# B301D.net
KiCad netlist of a schematic drawn in EAGLE
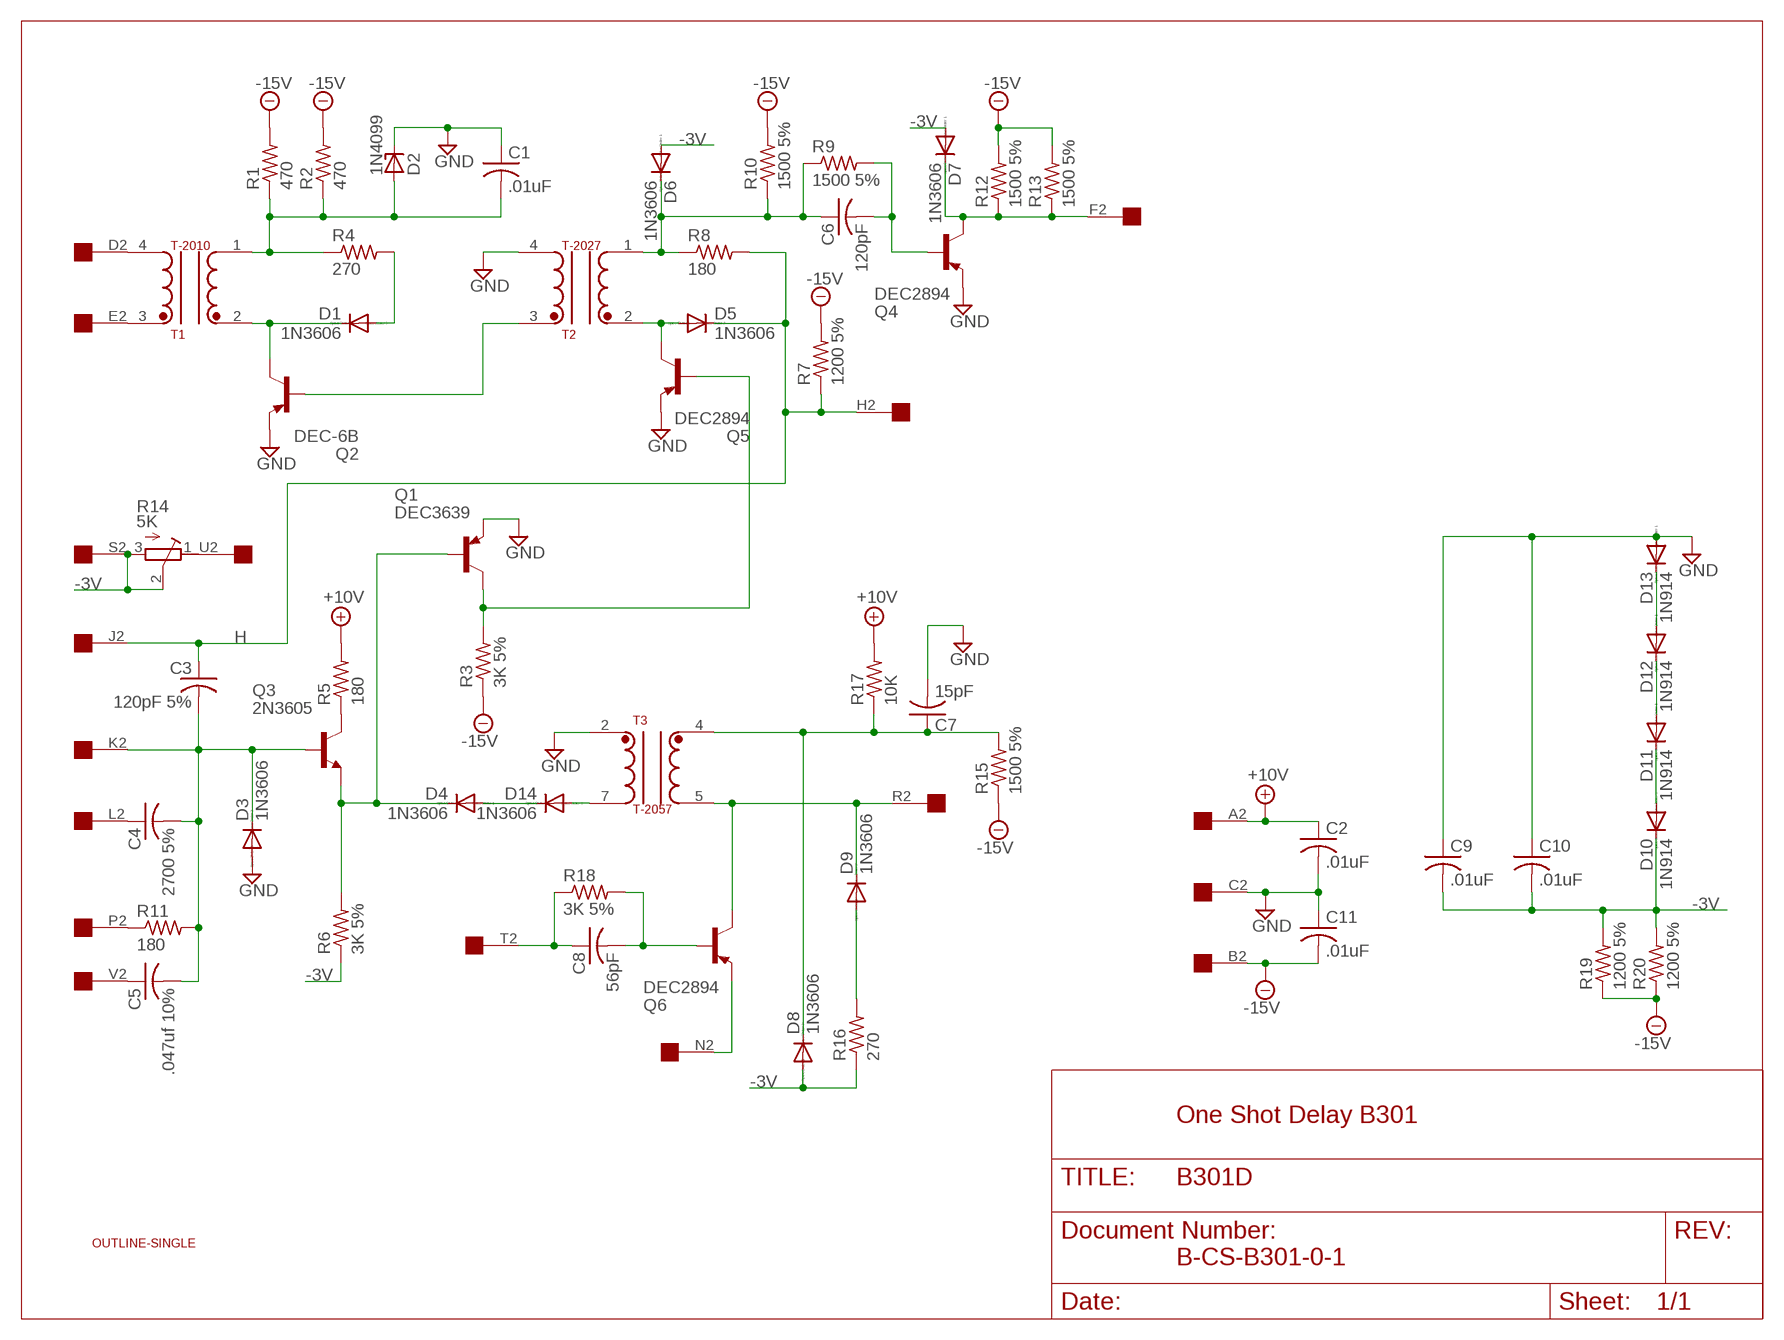
[diagram p0: schematic, sheet 1]

(export (version "E")
  (design (tool "Eeschema 10.0.6"))
  (components
    (comp (ref "C1")
      (value ".01uF")
      (footprint "eagle-import:C063-025X075")
      (libsource (lib "eagle-import") (part "C-US"))
    )
    (comp (ref "C2")
      (value ".01uF")
      (footprint "eagle-import:C063-025X075")
      (libsource (lib "eagle-import") (part "C-US"))
    )
    (comp (ref "C3")
      (value "120pF 5%")
      (footprint "eagle-import:C150-054X183")
      (libsource (lib "eagle-import") (part "C-US150-054X183"))
    )
    (comp (ref "C4")
      (value "2700 5%")
      (footprint "eagle-import:C102-043X133")
      (libsource (lib "eagle-import") (part "C-US102-043X133"))
    )
    (comp (ref "C5")
      (value ".047uf 10%")
      (footprint "eagle-import:C225-062X268")
      (libsource (lib "eagle-import") (part "C-US225-062X268"))
    )
    (comp (ref "C6")
      (value "120pF")
      (footprint "eagle-import:C150-054X183")
      (libsource (lib "eagle-import") (part "C-US150-054X183"))
    )
    (comp (ref "C7")
      (value "15pF")
      (footprint "eagle-import:C150-054X183")
      (libsource (lib "eagle-import") (part "C-US150-054X183"))
    )
    (comp (ref "C8")
      (value "56pF")
      (footprint "eagle-import:C150-054X183")
      (libsource (lib "eagle-import") (part "C-US150-054X183"))
    )
    (comp (ref "C9")
      (value ".01uF")
      (footprint "eagle-import:C063-025X075")
      (libsource (lib "eagle-import") (part "C-US"))
    )
    (comp (ref "C10")
      (value ".01uF")
      (footprint "eagle-import:C063-025X075")
      (libsource (lib "eagle-import") (part "C-US"))
    )
    (comp (ref "C11")
      (value ".01uF")
      (footprint "eagle-import:C063-025X075")
      (libsource (lib "eagle-import") (part "C-US"))
    )
    (comp (ref "D1")
      (value "1N3606")
      (footprint "eagle-import:DO35-10")
      (libsource (lib "eagle-import") (part "1N4148DO35-10"))
    )
    (comp (ref "D2")
      (value "1N4099")
      (footprint "eagle-import:DO35Z10")
      (libsource (lib "eagle-import") (part "ZENER-DIODEDO35Z10"))
    )
    (comp (ref "D3")
      (value "1N3606")
      (footprint "eagle-import:DO35-10")
      (libsource (lib "eagle-import") (part "1N4148DO35-10"))
    )
    (comp (ref "D4")
      (value "1N3606")
      (footprint "eagle-import:DO35-10")
      (libsource (lib "eagle-import") (part "1N4148DO35-10"))
    )
    (comp (ref "D5")
      (value "1N3606")
      (footprint "eagle-import:DO35-10")
      (libsource (lib "eagle-import") (part "1N4148DO35-10"))
    )
    (comp (ref "D6")
      (value "1N3606")
      (footprint "eagle-import:DO35-10")
      (libsource (lib "eagle-import") (part "1N4148DO35-10"))
    )
    (comp (ref "D7")
      (value "1N3606")
      (footprint "eagle-import:DO35-10")
      (libsource (lib "eagle-import") (part "1N4148DO35-10"))
    )
    (comp (ref "D8")
      (value "1N3606")
      (footprint "eagle-import:DO35-10")
      (libsource (lib "eagle-import") (part "1N4148DO35-10"))
    )
    (comp (ref "D9")
      (value "1N3606")
      (footprint "eagle-import:DO35-10")
      (libsource (lib "eagle-import") (part "1N4148DO35-10"))
    )
    (comp (ref "D10")
      (value "1N914")
      (footprint "eagle-import:DO35-10")
      (libsource (lib "eagle-import") (part "1N4148DO35-10"))
    )
    (comp (ref "D11")
      (value "1N914")
      (footprint "eagle-import:DO35-10")
      (libsource (lib "eagle-import") (part "1N4148DO35-10"))
    )
    (comp (ref "D12")
      (value "1N914")
      (footprint "eagle-import:DO35-10")
      (libsource (lib "eagle-import") (part "1N4148DO35-10"))
    )
    (comp (ref "D13")
      (value "1N914")
      (footprint "eagle-import:DO35-10")
      (libsource (lib "eagle-import") (part "1N4148DO35-10"))
    )
    (comp (ref "D14")
      (value "1N3606")
      (footprint "eagle-import:DO35-10")
      (libsource (lib "eagle-import") (part "1N4148DO35-10"))
    )
    (comp (ref "Q1")
      (value "DEC3639")
      (footprint "eagle-import:TO39")
      (libsource (lib "eagle-import") (part "2N2904"))
    )
    (comp (ref "Q2")
      (value "DEC-6B")
      (footprint "eagle-import:TO39")
      (libsource (lib "eagle-import") (part "2N2904"))
    )
    (comp (ref "Q3")
      (value "2N3605")
      (footprint "eagle-import:TO39")
      (libsource (lib "eagle-import") (part "-NPN-TO39-EBC2N2102"))
    )
    (comp (ref "Q4")
      (value "DEC2894")
      (footprint "eagle-import:TO39")
      (libsource (lib "eagle-import") (part "2N2904"))
    )
    (comp (ref "Q5")
      (value "DEC2894")
      (footprint "eagle-import:TO39")
      (libsource (lib "eagle-import") (part "2N2904"))
    )
    (comp (ref "Q6")
      (value "DEC2894")
      (footprint "eagle-import:TO39")
      (libsource (lib "eagle-import") (part "2N2904"))
    )
    (comp (ref "R1")
      (value "470")
      (footprint "eagle-import:0207_10")
      (libsource (lib "eagle-import") (part "R-US_0207/10"))
    )
    (comp (ref "R2")
      (value "470")
      (footprint "eagle-import:0207_10")
      (libsource (lib "eagle-import") (part "R-US_0207/10"))
    )
    (comp (ref "R3")
      (value "3K 5%")
      (footprint "eagle-import:0207_10")
      (libsource (lib "eagle-import") (part "R-US_0207/10"))
    )
    (comp (ref "R4")
      (value "270")
      (footprint "eagle-import:0207_10")
      (libsource (lib "eagle-import") (part "R-US_0207/10"))
    )
    (comp (ref "R5")
      (value "180")
      (footprint "eagle-import:0207_10")
      (libsource (lib "eagle-import") (part "R-US_0207/10"))
    )
    (comp (ref "R6")
      (value "3K 5%")
      (footprint "eagle-import:0207_10")
      (libsource (lib "eagle-import") (part "R-US_0207/10"))
    )
    (comp (ref "R7")
      (value "1200 5%")
      (footprint "eagle-import:0207_10")
      (libsource (lib "eagle-import") (part "R-US_0207/10"))
    )
    (comp (ref "R8")
      (value "180")
      (footprint "eagle-import:0207_10")
      (libsource (lib "eagle-import") (part "R-US_0207/10"))
    )
    (comp (ref "R9")
      (value "1500 5%")
      (footprint "eagle-import:0207_10")
      (libsource (lib "eagle-import") (part "R-US_0207/10"))
    )
    (comp (ref "R10")
      (value "1500 5%")
      (footprint "eagle-import:0207_10")
      (libsource (lib "eagle-import") (part "R-US_0207/10"))
    )
    (comp (ref "R11")
      (value "180")
      (footprint "eagle-import:0207_10")
      (libsource (lib "eagle-import") (part "R-US_0207/10"))
    )
    (comp (ref "R12")
      (value "1500 5%")
      (footprint "eagle-import:0207_10")
      (libsource (lib "eagle-import") (part "R-US_0207/10"))
    )
    (comp (ref "R13")
      (value "1500 5%")
      (footprint "eagle-import:0207_10")
      (libsource (lib "eagle-import") (part "R-US_0207/10"))
    )
    (comp (ref "R14")
      (value "5K")
      (footprint "eagle-import:3006Y")
      (libsource (lib "eagle-import") (part "275P"))
    )
    (comp (ref "R15")
      (value "1500 5%")
      (footprint "eagle-import:0207_10")
      (libsource (lib "eagle-import") (part "R-US_0207/10"))
    )
    (comp (ref "R16")
      (value "270")
      (footprint "eagle-import:0207_10")
      (libsource (lib "eagle-import") (part "R-US_0207/10"))
    )
    (comp (ref "R17")
      (value "10K")
      (footprint "eagle-import:0207_10")
      (libsource (lib "eagle-import") (part "R-US_0207/10"))
    )
    (comp (ref "R18")
      (value "3K 5%")
      (footprint "eagle-import:0207_10")
      (libsource (lib "eagle-import") (part "R-US_0207/10"))
    )
    (comp (ref "R19")
      (value "1200 5%")
      (footprint "eagle-import:0207_10")
      (libsource (lib "eagle-import") (part "R-US_0207/10"))
    )
    (comp (ref "R20")
      (value "1200 5%")
      (footprint "eagle-import:0207_10")
      (libsource (lib "eagle-import") (part "R-US_0207/10"))
    )
    (comp (ref "T1")
      (value "T-2010")
      (footprint "eagle-import:TRANSFORMER2")
      (libsource (lib "eagle-import") (part "T-2010"))
    )
    (comp (ref "T2")
      (value "T-2027")
      (footprint "eagle-import:TRANSFORMER2")
      (libsource (lib "eagle-import") (part "T-2010"))
    )
    (comp (ref "T3")
      (value "T-2057")
      (footprint "eagle-import:TRANSFORMER")
      (libsource (lib "eagle-import") (part "T-2037"))
    )
    (comp (ref "U$1")
      (value "OUTLINE-SINGLE")
      (footprint "eagle-import:SINGLE")
      (libsource (lib "eagle-import") (part "OUTLINE-SINGLE"))
    )
    (comp (ref "U$2")
      (value "EDGE-1")
      (footprint "eagle-import:EDGE-CON1")
      (libsource (lib "eagle-import") (part "EDGE-1"))
    )
  )
  (nets
    (net (code "1") (name "+10V") (class "Default")
      (node (ref "C2") (pin "1") (pinfunction "1_1") (pintype "passive"))
      (node (ref "R17") (pin "2") (pinfunction "2_2") (pintype "passive"))
      (node (ref "R5") (pin "2") (pinfunction "2_2") (pintype "passive"))
      (node (ref "U$2") (pin "A2") (pinfunction "1_A2") (pintype "bidirectional"))
    )
    (net (code "2") (name "-15V") (class "Default")
      (node (ref "C11") (pin "2") (pinfunction "2_2") (pintype "passive"))
      (node (ref "R1") (pin "2") (pinfunction "2_2") (pintype "passive"))
      (node (ref "R10") (pin "2") (pinfunction "2_2") (pintype "passive"))
      (node (ref "R12") (pin "2") (pinfunction "2_2") (pintype "passive"))
      (node (ref "R13") (pin "2") (pinfunction "2_2") (pintype "passive"))
      (node (ref "R15") (pin "1") (pinfunction "1_1") (pintype "passive"))
      (node (ref "R19") (pin "1") (pinfunction "1_1") (pintype "passive"))
      (node (ref "R2") (pin "2") (pinfunction "2_2") (pintype "passive"))
      (node (ref "R20") (pin "1") (pinfunction "1_1") (pintype "passive"))
      (node (ref "R3") (pin "1") (pinfunction "1_1") (pintype "passive"))
      (node (ref "R7") (pin "2") (pinfunction "2_2") (pintype "passive"))
      (node (ref "U$2") (pin "B2") (pinfunction "1_B2") (pintype "bidirectional"))
    )
    (net (code "3") (name "/-3V") (class "Default")
      (node (ref "C10") (pin "2") (pinfunction "2_2") (pintype "passive"))
      (node (ref "C9") (pin "2") (pinfunction "2_2") (pintype "passive"))
      (node (ref "D10") (pin "C") (pinfunction "C_C") (pintype "passive"))
      (node (ref "D6") (pin "A") (pinfunction "A_A") (pintype "passive"))
      (node (ref "D7") (pin "A") (pinfunction "A_A") (pintype "passive"))
      (node (ref "D8") (pin "A") (pinfunction "A_A") (pintype "passive"))
      (node (ref "R14") (pin "2") (pinfunction "S_2") (pintype "passive"))
      (node (ref "R14") (pin "3") (pinfunction "E_3") (pintype "passive"))
      (node (ref "R16") (pin "1") (pinfunction "1_1") (pintype "passive"))
      (node (ref "R19") (pin "2") (pinfunction "2_2") (pintype "passive"))
      (node (ref "R20") (pin "2") (pinfunction "2_2") (pintype "passive"))
      (node (ref "R6") (pin "1") (pinfunction "1_1") (pintype "passive"))
      (node (ref "U$2") (pin "S2") (pinfunction "1_S2") (pintype "bidirectional"))
    )
    (net (code "4") (name "/H") (class "Default")
      (node (ref "C3") (pin "1") (pinfunction "1_1") (pintype "passive"))
      (node (ref "D5") (pin "C") (pinfunction "C_C") (pintype "passive"))
      (node (ref "R7") (pin "1") (pinfunction "1_1") (pintype "passive"))
      (node (ref "R8") (pin "2") (pinfunction "2_2") (pintype "passive"))
      (node (ref "U$2") (pin "H2") (pinfunction "1_H2") (pintype "bidirectional"))
      (node (ref "U$2") (pin "J2") (pinfunction "1_J2") (pintype "bidirectional"))
    )
    (net (code "5") (name "GND") (class "Default")
      (node (ref "C1") (pin "1") (pinfunction "1_1") (pintype "passive"))
      (node (ref "C10") (pin "1") (pinfunction "1_1") (pintype "passive"))
      (node (ref "C11") (pin "1") (pinfunction "1_1") (pintype "passive"))
      (node (ref "C2") (pin "2") (pinfunction "2_2") (pintype "passive"))
      (node (ref "C7") (pin "2") (pinfunction "2_2") (pintype "passive"))
      (node (ref "C9") (pin "1") (pinfunction "1_1") (pintype "passive"))
      (node (ref "D13") (pin "A") (pinfunction "A_A") (pintype "passive"))
      (node (ref "D2") (pin "C") (pinfunction "C_C") (pintype "passive"))
      (node (ref "D3") (pin "A") (pinfunction "A_A") (pintype "passive"))
      (node (ref "Q1") (pin "1") (pinfunction "E_1") (pintype "passive"))
      (node (ref "Q2") (pin "1") (pinfunction "E_1") (pintype "passive"))
      (node (ref "Q4") (pin "1") (pinfunction "E_1") (pintype "passive"))
      (node (ref "Q5") (pin "1") (pinfunction "E_1") (pintype "passive"))
      (node (ref "T2") (pin "4") (pinfunction "P$7_4") (pintype "passive"))
      (node (ref "T3") (pin "2") (pinfunction "P$2_2") (pintype "passive"))
      (node (ref "U$2") (pin "C2") (pinfunction "1_C2") (pintype "bidirectional"))
    )
    (net (code "6") (name "Net-(D1-PadA)") (class "Default")
      (node (ref "D1") (pin "A") (pinfunction "A_A") (pintype "passive"))
      (node (ref "R4") (pin "2") (pinfunction "2_2") (pintype "passive"))
    )
    (net (code "7") (name "Net-(D9-PadA)") (class "Default")
      (node (ref "D9") (pin "A") (pinfunction "A_A") (pintype "passive"))
      (node (ref "R16") (pin "2") (pinfunction "2_2") (pintype "passive"))
    )
    (net (code "8") (name "Net-(D10-PadA)") (class "Default")
      (node (ref "D10") (pin "A") (pinfunction "A_A") (pintype "passive"))
      (node (ref "D11") (pin "C") (pinfunction "C_C") (pintype "passive"))
    )
    (net (code "9") (name "Net-(D11-PadA)") (class "Default")
      (node (ref "D11") (pin "A") (pinfunction "A_A") (pintype "passive"))
      (node (ref "D12") (pin "C") (pinfunction "C_C") (pintype "passive"))
    )
    (net (code "10") (name "Net-(D12-PadA)") (class "Default")
      (node (ref "D12") (pin "A") (pinfunction "A_A") (pintype "passive"))
      (node (ref "D13") (pin "C") (pinfunction "C_C") (pintype "passive"))
    )
    (net (code "11") (name "Net-(D14-PadC)") (class "Default")
      (node (ref "D14") (pin "C") (pinfunction "C_C") (pintype "passive"))
      (node (ref "D4") (pin "A") (pinfunction "A_A") (pintype "passive"))
    )
    (net (code "12") (name "Net-(Q1-B)") (class "Default")
      (node (ref "D4") (pin "C") (pinfunction "C_C") (pintype "passive"))
      (node (ref "Q1") (pin "2") (pinfunction "B_2") (pintype "passive"))
      (node (ref "Q3") (pin "1") (pinfunction "E_1") (pintype "passive"))
      (node (ref "R6") (pin "2") (pinfunction "2_2") (pintype "passive"))
    )
    (net (code "13") (name "Net-(Q1-C)") (class "Default")
      (node (ref "Q1") (pin "3") (pinfunction "C_3") (pintype "passive"))
      (node (ref "Q5") (pin "2") (pinfunction "B_2") (pintype "passive"))
      (node (ref "R3") (pin "2") (pinfunction "2_2") (pintype "passive"))
    )
    (net (code "14") (name "Net-(Q2-B)") (class "Default")
      (node (ref "Q2") (pin "2") (pinfunction "B_2") (pintype "passive"))
      (node (ref "T2") (pin "3") (pinfunction "P$2_3") (pintype "passive"))
    )
    (net (code "15") (name "Net-(Q2-C)") (class "Default")
      (node (ref "D1") (pin "C") (pinfunction "C_C") (pintype "passive"))
      (node (ref "Q2") (pin "3") (pinfunction "C_3") (pintype "passive"))
      (node (ref "T1") (pin "2") (pinfunction "P$4_2") (pintype "passive"))
    )
    (net (code "16") (name "Net-(Q3-B)") (class "Default")
      (node (ref "C3") (pin "2") (pinfunction "2_2") (pintype "passive"))
      (node (ref "C4") (pin "2") (pinfunction "2_2") (pintype "passive"))
      (node (ref "C5") (pin "2") (pinfunction "2_2") (pintype "passive"))
      (node (ref "D3") (pin "C") (pinfunction "C_C") (pintype "passive"))
      (node (ref "Q3") (pin "2") (pinfunction "B_2") (pintype "passive"))
      (node (ref "R11") (pin "2") (pinfunction "2_2") (pintype "passive"))
      (node (ref "U$2") (pin "K2") (pinfunction "1_K2") (pintype "bidirectional"))
    )
    (net (code "17") (name "Net-(Q3-C)") (class "Default")
      (node (ref "Q3") (pin "3") (pinfunction "C_3") (pintype "passive"))
      (node (ref "R5") (pin "1") (pinfunction "1_1") (pintype "passive"))
    )
    (net (code "18") (name "Net-(Q4-B)") (class "Default")
      (node (ref "C6") (pin "2") (pinfunction "2_2") (pintype "passive"))
      (node (ref "Q4") (pin "2") (pinfunction "B_2") (pintype "passive"))
      (node (ref "R9") (pin "2") (pinfunction "2_2") (pintype "passive"))
    )
    (net (code "19") (name "Net-(Q4-C)") (class "Default")
      (node (ref "D7") (pin "C") (pinfunction "C_C") (pintype "passive"))
      (node (ref "Q4") (pin "3") (pinfunction "C_3") (pintype "passive"))
      (node (ref "R12") (pin "1") (pinfunction "1_1") (pintype "passive"))
      (node (ref "R13") (pin "1") (pinfunction "1_1") (pintype "passive"))
      (node (ref "U$2") (pin "F2") (pinfunction "1_F2") (pintype "bidirectional"))
    )
    (net (code "20") (name "Net-(Q5-C)") (class "Default")
      (node (ref "D5") (pin "A") (pinfunction "A_A") (pintype "passive"))
      (node (ref "Q5") (pin "3") (pinfunction "C_3") (pintype "passive"))
      (node (ref "T2") (pin "2") (pinfunction "P$4_2") (pintype "passive"))
    )
    (net (code "21") (name "Net-(Q6-B)") (class "Default")
      (node (ref "C8") (pin "2") (pinfunction "2_2") (pintype "passive"))
      (node (ref "Q6") (pin "2") (pinfunction "B_2") (pintype "passive"))
      (node (ref "R18") (pin "2") (pinfunction "2_2") (pintype "passive"))
    )
    (net (code "22") (name "Net-(Q6-C)") (class "Default")
      (node (ref "D9") (pin "C") (pinfunction "C_C") (pintype "passive"))
      (node (ref "Q6") (pin "3") (pinfunction "C_3") (pintype "passive"))
      (node (ref "T3") (pin "5") (pinfunction "P$5_5") (pintype "passive"))
      (node (ref "U$2") (pin "R2") (pinfunction "1_R2") (pintype "bidirectional"))
    )
    (net (code "23") (name "Net-(Q6-E)") (class "Default")
      (node (ref "Q6") (pin "1") (pinfunction "E_1") (pintype "passive"))
      (node (ref "U$2") (pin "N2") (pinfunction "1_N2") (pintype "bidirectional"))
    )
    (net (code "24") (name "Net-(R14-A)") (class "Default")
      (node (ref "R14") (pin "1") (pinfunction "A_1") (pintype "passive"))
      (node (ref "U$2") (pin "U2") (pinfunction "1_U2") (pintype "bidirectional"))
    )
    (net (code "25") (name "Net-(T1-P$2)") (class "Default")
      (node (ref "T1") (pin "3") (pinfunction "P$2_3") (pintype "passive"))
      (node (ref "U$2") (pin "E2") (pinfunction "1_E2") (pintype "bidirectional"))
    )
    (net (code "26") (name "Net-(T1-P$5)") (class "Default")
      (node (ref "C1") (pin "2") (pinfunction "2_2") (pintype "passive"))
      (node (ref "D2") (pin "A") (pinfunction "A_A") (pintype "passive"))
      (node (ref "R1") (pin "1") (pinfunction "1_1") (pintype "passive"))
      (node (ref "R2") (pin "1") (pinfunction "1_1") (pintype "passive"))
      (node (ref "R4") (pin "1") (pinfunction "1_1") (pintype "passive"))
      (node (ref "T1") (pin "1") (pinfunction "P$5_1") (pintype "passive"))
    )
    (net (code "27") (name "Net-(T1-P$7)") (class "Default")
      (node (ref "T1") (pin "4") (pinfunction "P$7_4") (pintype "passive"))
      (node (ref "U$2") (pin "D2") (pinfunction "1_D2") (pintype "bidirectional"))
    )
    (net (code "28") (name "Net-(T2-P$5)") (class "Default")
      (node (ref "C6") (pin "1") (pinfunction "1_1") (pintype "passive"))
      (node (ref "D6") (pin "C") (pinfunction "C_C") (pintype "passive"))
      (node (ref "R10") (pin "1") (pinfunction "1_1") (pintype "passive"))
      (node (ref "R8") (pin "1") (pinfunction "1_1") (pintype "passive"))
      (node (ref "R9") (pin "1") (pinfunction "1_1") (pintype "passive"))
      (node (ref "T2") (pin "1") (pinfunction "P$5_1") (pintype "passive"))
    )
    (net (code "29") (name "Net-(T3-P$4)") (class "Default")
      (node (ref "C7") (pin "1") (pinfunction "1_1") (pintype "passive"))
      (node (ref "D8") (pin "C") (pinfunction "C_C") (pintype "passive"))
      (node (ref "R15") (pin "2") (pinfunction "2_2") (pintype "passive"))
      (node (ref "R17") (pin "1") (pinfunction "1_1") (pintype "passive"))
      (node (ref "T3") (pin "4") (pinfunction "P$4_4") (pintype "passive"))
    )
    (net (code "30") (name "Net-(T3-P$7)") (class "Default")
      (node (ref "D14") (pin "A") (pinfunction "A_A") (pintype "passive"))
      (node (ref "T3") (pin "7") (pinfunction "P$7_7") (pintype "passive"))
    )
    (net (code "31") (name "Net-(U$2J-1)") (class "Default")
      (node (ref "C4") (pin "1") (pinfunction "1_1") (pintype "passive"))
      (node (ref "U$2") (pin "L2") (pinfunction "1_L2") (pintype "bidirectional"))
    )
    (net (code "32") (name "Net-(U$2M-1)") (class "Default")
      (node (ref "R11") (pin "1") (pinfunction "1_1") (pintype "passive"))
      (node (ref "U$2") (pin "P2") (pinfunction "1_P2") (pintype "bidirectional"))
    )
    (net (code "33") (name "Net-(U$2P-1)") (class "Default")
      (node (ref "C8") (pin "1") (pinfunction "1_1") (pintype "passive"))
      (node (ref "R18") (pin "1") (pinfunction "1_1") (pintype "passive"))
      (node (ref "U$2") (pin "T2") (pinfunction "1_T2") (pintype "bidirectional"))
    )
    (net (code "34") (name "Net-(U$2R-1)") (class "Default")
      (node (ref "C5") (pin "1") (pinfunction "1_1") (pintype "passive"))
      (node (ref "U$2") (pin "V2") (pinfunction "1_V2") (pintype "bidirectional"))
    )
  )
)
